# Power_Distribution_-_Power_Path_2_Parall.net
KiCad netlist of a schematic drawn in Altium Designer
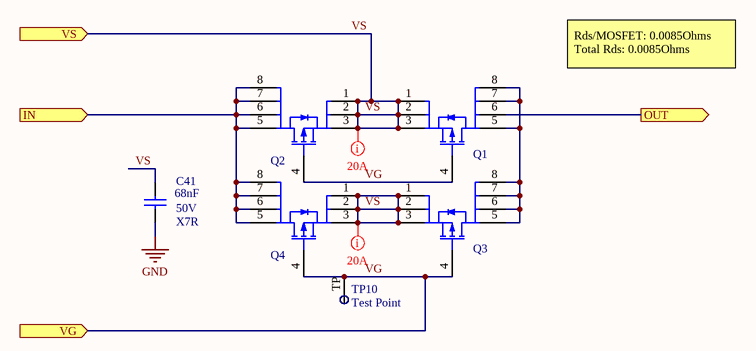
[diagram p0: Power Distribution - Power Path 2 Parallel MOSFET.SchDoc]

(export (version "E")
  (design (tool "Eeschema 10.0.6"))
  (components
    (comp (ref "C41")
      (value "68nF")
      (footprint "CAP, 0603")
      (description "0.068µF 50V Ceramic Capacitor X7R 0603 (1608 Metric) 0.063\" L x 0.032\" W (1.60mm x 0.80mm)")
      (fields
        (field (name "MANUFACTURER") "Murata")
        (field (name "MANUFACTURER PART NUMBER") "GCM188R71H683KA57D")
        (field (name "VOLTAGE RATING") "50V")
        (field (name "DIELECTRIC") "X7R")
      )
      (libsource (lib "Schematic Diagrams") (part "CAP CER 0.068UF 10% 50V X7R 0603"))
    )
    (comp (ref "Q1")
      (value "MOSFET P-CH PWR56 40V 4.9 MOHM")
      (footprint "PMOS PWR56 40V 4.9 MOHM")
      (description "P-Channel 16V 2.5A (Ta) 650mW (Ta) Surface Mount X2-DFN2015-3")
      (libsource (lib "Schematic Diagrams") (part "MOSFET P-CH PWR56 40V 4.9 MOHM"))
    )
    (comp (ref "Q2")
      (value "MOSFET P-CH PWR56 40V 4.9 MOHM")
      (footprint "PMOS PWR56 40V 4.9 MOHM")
      (description "P-Channel 16V 2.5A (Ta) 650mW (Ta) Surface Mount X2-DFN2015-3")
      (libsource (lib "Schematic Diagrams") (part "MOSFET P-CH PWR56 40V 4.9 MOHM"))
    )
    (comp (ref "Q3")
      (value "MOSFET P-CH PWR56 40V 4.9 MOHM")
      (footprint "PMOS PWR56 40V 4.9 MOHM")
      (description "P-Channel 16V 2.5A (Ta) 650mW (Ta) Surface Mount X2-DFN2015-3")
      (libsource (lib "Schematic Diagrams") (part "MOSFET P-CH PWR56 40V 4.9 MOHM"))
    )
    (comp (ref "Q4")
      (value "MOSFET P-CH PWR56 40V 4.9 MOHM")
      (footprint "PMOS PWR56 40V 4.9 MOHM")
      (description "P-Channel 16V 2.5A (Ta) 650mW (Ta) Surface Mount X2-DFN2015-3")
      (libsource (lib "Schematic Diagrams") (part "MOSFET P-CH PWR56 40V 4.9 MOHM"))
    )
    (comp (ref "TP10")
      (value "Test Point")
      (footprint "Test Point")
      (libsource (lib "Schematic Diagrams") (part "Test Point"))
    )
  )
  (nets
    (net (code "1") (name "/IN") (class "Default")
      (node (ref "Q2") (pin "5") (pinfunction "D_5") (pintype "passive"))
      (node (ref "Q2") (pin "6") (pinfunction "D_6") (pintype "passive"))
      (node (ref "Q2") (pin "7") (pinfunction "D_7") (pintype "passive"))
      (node (ref "Q2") (pin "8") (pinfunction "D_8") (pintype "passive"))
      (node (ref "Q4") (pin "5") (pinfunction "D_5") (pintype "passive"))
      (node (ref "Q4") (pin "6") (pinfunction "D_6") (pintype "passive"))
      (node (ref "Q4") (pin "7") (pinfunction "D_7") (pintype "passive"))
      (node (ref "Q4") (pin "8") (pinfunction "D_8") (pintype "passive"))
    )
    (net (code "2") (name "/OUT") (class "Default")
      (node (ref "Q1") (pin "6") (pinfunction "D_6") (pintype "passive"))
    )
    (net (code "3") (name "/VG") (class "Default")
      (node (ref "Q1") (pin "4") (pinfunction "G_4") (pintype "passive"))
      (node (ref "Q2") (pin "4") (pinfunction "G_4") (pintype "passive"))
      (node (ref "Q3") (pin "4") (pinfunction "G_4") (pintype "passive"))
      (node (ref "Q4") (pin "4") (pinfunction "G_4") (pintype "passive"))
      (node (ref "TP10") (pin "TP") (pinfunction "1_TP") (pintype "passive"))
    )
    (net (code "4") (name "/VS") (class "Default")
      (node (ref "C41") (pin "1") (pinfunction "1_1") (pintype "passive"))
      (node (ref "Q1") (pin "1") (pinfunction "S_1") (pintype "passive"))
      (node (ref "Q1") (pin "2") (pinfunction "S_2") (pintype "passive"))
      (node (ref "Q1") (pin "3") (pinfunction "S_3") (pintype "passive"))
      (node (ref "Q2") (pin "1") (pinfunction "S_1") (pintype "passive"))
      (node (ref "Q2") (pin "2") (pinfunction "S_2") (pintype "passive"))
      (node (ref "Q2") (pin "3") (pinfunction "S_3") (pintype "passive"))
      (node (ref "Q3") (pin "1") (pinfunction "S_1") (pintype "passive"))
      (node (ref "Q3") (pin "2") (pinfunction "S_2") (pintype "passive"))
      (node (ref "Q3") (pin "3") (pinfunction "S_3") (pintype "passive"))
      (node (ref "Q4") (pin "1") (pinfunction "S_1") (pintype "passive"))
      (node (ref "Q4") (pin "2") (pinfunction "S_2") (pintype "passive"))
      (node (ref "Q4") (pin "3") (pinfunction "S_3") (pintype "passive"))
    )
    (net (code "5") (name "GND") (class "Default")
      (node (ref "C41") (pin "2") (pinfunction "2_2") (pintype "passive"))
    )
    (net (code "6") (name "Net-(Q1-D-Pad5)") (class "Default")
      (node (ref "Q1") (pin "5") (pinfunction "D_5") (pintype "passive"))
      (node (ref "Q1") (pin "7") (pinfunction "D_7") (pintype "passive"))
      (node (ref "Q1") (pin "8") (pinfunction "D_8") (pintype "passive"))
      (node (ref "Q3") (pin "5") (pinfunction "D_5") (pintype "passive"))
      (node (ref "Q3") (pin "6") (pinfunction "D_6") (pintype "passive"))
      (node (ref "Q3") (pin "7") (pinfunction "D_7") (pintype "passive"))
      (node (ref "Q3") (pin "8") (pinfunction "D_8") (pintype "passive"))
    )
  )
)
